# IMU.net
KiCad netlist of a schematic drawn in Altium Designer
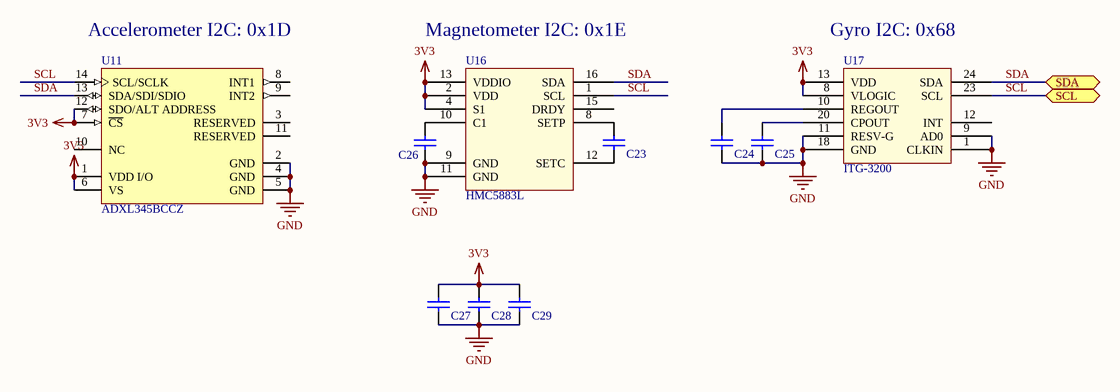
[diagram p0: IMU.SchDoc]

(export (version "E")
  (design (tool "Eeschema 10.0.6"))
  (components
    (comp (ref "C23")
      (value "CAP 220nF 25V 0402(1005)")
      (footprint "CAPC0402(1005)60_N")
      (description "CAP 220nF 25V ±20% 0402 (1005 Metric) Thickness 0.6mm SMD")
      (fields (field (name "TOLERANCE") "±20%"))
      (libsource (lib "Altium Content Vault") (part "CMP-1034-02093-1"))
    )
    (comp (ref "C24")
      (value "CAP 100nF 25V 0402(1005)")
      (footprint "CAPC0402(1005)60_N")
      (description "CAP 100nF 25V ±20% 0402 (1005 Metric) Thickness 0.6mm SMD")
      (fields (field (name "TOLERANCE") "±20%"))
      (libsource (lib "Altium Content Vault") (part "CAP"))
    )
    (comp (ref "C25")
      (value "CAP 2.2nF 25V 0402(1005)")
      (footprint "CAPC0402(1005)60_N")
      (description "CAP 2.2nF 25V ±20% 0402 (1005 Metric) Thickness 0.6mm SMD")
      (fields (field (name "TOLERANCE") "±20%"))
      (libsource (lib "Altium Content Vault") (part "CMP-1034-01740-1"))
    )
    (comp (ref "C26")
      (value "CAP 4.7uF 6.3V 0402(1005)")
      (footprint "CAPC0402(1005)60_N")
      (description "CAP 4.7uF 6.3V ±20% 0402 (1005 Metric) Thickness 0.6mm SMD")
      (fields (field (name "TOLERANCE") "±20%"))
      (libsource (lib "Altium Content Vault") (part "CAP"))
    )
    (comp (ref "C27")
      (value "CAP 100nF 25V 0402(1005)")
      (footprint "CAPC0402(1005)60_N")
      (description "CAP 100nF 25V ±20% 0402 (1005 Metric) Thickness 0.6mm SMD")
      (fields (field (name "TOLERANCE") "±20%"))
      (libsource (lib "Altium Content Vault") (part "CMP-1034-02073-1"))
    )
    (comp (ref "C28")
      (value "CAP 100nF 25V 0402(1005)")
      (footprint "CAPC0402(1005)60_N")
      (description "CAP 100nF 25V ±20% 0402 (1005 Metric) Thickness 0.6mm SMD")
      (fields (field (name "TOLERANCE") "±20%"))
      (libsource (lib "Altium Content Vault") (part "CMP-1034-02073-1"))
    )
    (comp (ref "C29")
      (value "CAP 100nF 25V 0402(1005)")
      (footprint "CAPC0402(1005)60_N")
      (description "CAP 100nF 25V ±20% 0402 (1005 Metric) Thickness 0.6mm SMD")
      (fields (field (name "TOLERANCE") "±20%"))
      (libsource (lib "Altium Content Vault") (part "CMP-1034-02073-1"))
    )
    (comp (ref "U11")
      (value "ADXL345BCCZ")
      (footprint "ADI-CC-14-1_V")
      (fields (field (name "MANUFACTURER") "Analog Devices"))
      (libsource (lib "Altium Content Vault") (part "CMP-0885-00027-1"))
    )
    (comp (ref "U16") (value "HMC5883L") (footprint "HMC5883L") (libsource (lib "Centum") (part "HMC5883L")))
    (comp (ref "U17") (value "ITG-3200") (footprint "ITG-3200") (libsource (lib "Centum") (part "ITG-3200")))
  )
  (nets
    (net (code "1") (name "/SCL") (class "Default")
      (node (ref "U11") (pin "14") (pinfunction "SCL/SCLK_14") (pintype "input"))
      (node (ref "U16") (pin "1") (pinfunction "SCL_1") (pintype "passive"))
      (node (ref "U17") (pin "23") (pinfunction "SCL_23") (pintype "passive"))
    )
    (net (code "2") (name "/SDA") (class "Default")
      (node (ref "U11") (pin "13") (pinfunction "SDA/SDI/SDIO_13") (pintype "bidirectional"))
      (node (ref "U16") (pin "16") (pinfunction "SDA_16") (pintype "passive"))
      (node (ref "U17") (pin "24") (pinfunction "SDA_24") (pintype "passive"))
    )
    (net (code "3") (name "3V3") (class "Default")
      (node (ref "C27") (pin "2") (pinfunction "2_2") (pintype "passive"))
      (node (ref "C28") (pin "2") (pinfunction "2_2") (pintype "passive"))
      (node (ref "C29") (pin "2") (pinfunction "2_2") (pintype "passive"))
      (node (ref "U11") (pin "1") (pinfunction "VDD_I/O_1") (pintype "power_in"))
      (node (ref "U11") (pin "12") (pinfunction "SDO/ALT_ADDRESS_12") (pintype "bidirectional"))
      (node (ref "U11") (pin "6") (pinfunction "VS_6") (pintype "power_in"))
      (node (ref "U11") (pin "7") (pinfunction "~{CS}_7") (pintype "input"))
      (node (ref "U16") (pin "13") (pinfunction "VDDIO_13") (pintype "passive"))
      (node (ref "U16") (pin "2") (pinfunction "VDD_2") (pintype "passive"))
      (node (ref "U16") (pin "4") (pinfunction "S1_4") (pintype "passive"))
      (node (ref "U17") (pin "13") (pinfunction "VDD_13") (pintype "passive"))
      (node (ref "U17") (pin "8") (pinfunction "VLOGIC_8") (pintype "passive"))
    )
    (net (code "4") (name "GND") (class "Default")
      (node (ref "C24") (pin "1") (pinfunction "1_1") (pintype "passive"))
      (node (ref "C25") (pin "1") (pinfunction "1_1") (pintype "passive"))
      (node (ref "C26") (pin "1") (pinfunction "1_1") (pintype "passive"))
      (node (ref "C27") (pin "1") (pinfunction "1_1") (pintype "passive"))
      (node (ref "C28") (pin "1") (pinfunction "1_1") (pintype "passive"))
      (node (ref "C29") (pin "1") (pinfunction "1_1") (pintype "passive"))
      (node (ref "U11") (pin "2") (pinfunction "GND_2") (pintype "power_in"))
      (node (ref "U11") (pin "4") (pinfunction "GND_4") (pintype "power_in"))
      (node (ref "U11") (pin "5") (pinfunction "GND_5") (pintype "power_in"))
      (node (ref "U16") (pin "11") (pinfunction "GND_11") (pintype "passive"))
      (node (ref "U16") (pin "9") (pinfunction "GND_9") (pintype "passive"))
      (node (ref "U17") (pin "1") (pinfunction "CLKIN_1") (pintype "passive"))
      (node (ref "U17") (pin "11") (pinfunction "RESV-G_11") (pintype "passive"))
      (node (ref "U17") (pin "18") (pinfunction "GND_18") (pintype "passive"))
      (node (ref "U17") (pin "9") (pinfunction "AD0_9") (pintype "passive"))
    )
    (net (code "5") (name "Net-(U16-C1)") (class "Default")
      (node (ref "C26") (pin "2") (pinfunction "2_2") (pintype "passive"))
      (node (ref "U16") (pin "10") (pinfunction "C1_10") (pintype "passive"))
    )
    (net (code "6") (name "Net-(U16-SETC)") (class "Default")
      (node (ref "C23") (pin "1") (pinfunction "1_1") (pintype "passive"))
      (node (ref "U16") (pin "12") (pinfunction "SETC_12") (pintype "passive"))
    )
    (net (code "7") (name "Net-(U16-SETP)") (class "Default")
      (node (ref "C23") (pin "2") (pinfunction "2_2") (pintype "passive"))
      (node (ref "U16") (pin "8") (pinfunction "SETP_8") (pintype "passive"))
    )
    (net (code "8") (name "Net-(U17-CPOUT)") (class "Default")
      (node (ref "C25") (pin "2") (pinfunction "2_2") (pintype "passive"))
      (node (ref "U17") (pin "20") (pinfunction "CPOUT_20") (pintype "passive"))
    )
    (net (code "9") (name "Net-(U17-REGOUT)") (class "Default")
      (node (ref "C24") (pin "2") (pinfunction "2_2") (pintype "passive"))
      (node (ref "U17") (pin "10") (pinfunction "REGOUT_10") (pintype "passive"))
    )
    (net (code "10") (name "unconnected-(U11-INT1-Pad8)") (class "Default")
      (node (ref "U11") (pin "8") (pinfunction "INT1_8") (pintype "output"))
    )
    (net (code "11") (name "unconnected-(U11-INT2-Pad9)") (class "Default")
      (node (ref "U11") (pin "9") (pinfunction "INT2_9") (pintype "output"))
    )
    (net (code "12") (name "unconnected-(U11-NC-Pad10)") (class "Default")
      (node (ref "U11") (pin "10") (pinfunction "NC_10") (pintype "passive"))
    )
    (net (code "13") (name "unconnected-(U11-RESERVED-Pad3)") (class "Default")
      (node (ref "U11") (pin "3") (pinfunction "RESERVED_3") (pintype "passive"))
    )
    (net (code "14") (name "unconnected-(U11-RESERVED-Pad11)") (class "Default")
      (node (ref "U11") (pin "11") (pinfunction "RESERVED_11") (pintype "passive"))
    )
    (net (code "15") (name "unconnected-(U16-DRDY-Pad15)") (class "Default")
      (node (ref "U16") (pin "15") (pinfunction "DRDY_15") (pintype "passive"))
    )
    (net (code "16") (name "unconnected-(U17-INT-Pad12)") (class "Default")
      (node (ref "U17") (pin "12") (pinfunction "INT_12") (pintype "passive"))
    )
  )
)
